# STML451RE.net
KiCad netlist of a schematic drawn in EAGLE
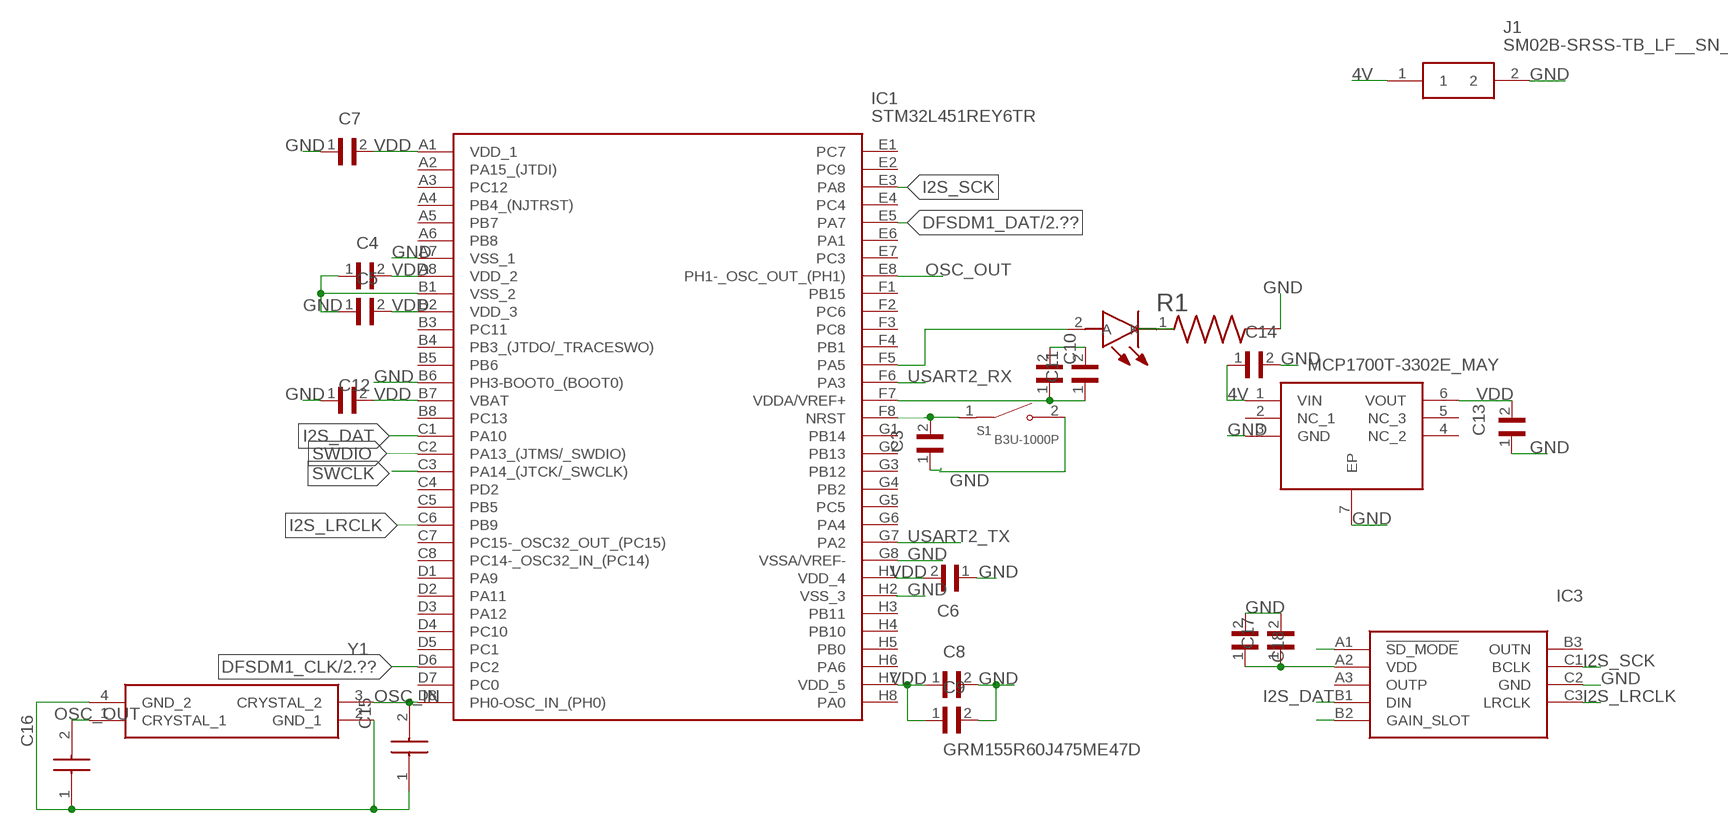
[diagram p0: schematic, sheet 1]
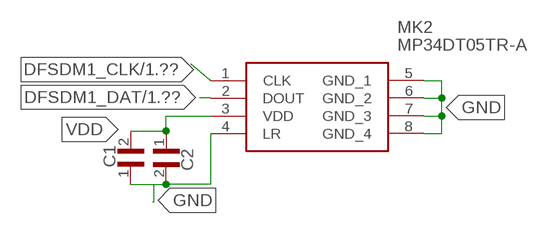
[diagram p1: schematic, sheet 2]

(export (version "E")
  (design (tool "Eeschema 10.0.6"))
  (components
    (comp (ref "C1")
      (value "GRM033C80J104KE15D")
      (footprint "eagle-import:CAPC0603X33N")
      (fields (field (name "DIGI-KEY_PART_NUMBER") "490-10390-1-ND") (field (name "MF") "Murata Electronics"))
      (libsource (lib "eagle-import") (part "GRM033C80J104KE15D"))
    )
    (comp (ref "C2")
      (value "JMK105C6105KV-F")
      (footprint "eagle-import:CAPC1005X55N")
      (fields (field (name "DIGI-KEY_PART_NUMBER") "587-3381-1-ND") (field (name "MF") "Taiyo Yuden"))
      (libsource (lib "eagle-import") (part "JMK105C6105KV-F"))
    )
    (comp (ref "MK2")
      (value "MP34DT05TR-A")
      (footprint "eagle-import:MP34DT05TRA")
      (fields (field (name "MOUSER_PART_NUMBER") "511-MP34DT05TR-A"))
      (libsource (lib "eagle-import") (part "MP34DT05TR-A"))
    )
    (comp (ref "C3")
      (value "GRM033C80J104KE15D")
      (footprint "eagle-import:CAPC0603X33N")
      (fields (field (name "DIGI-KEY_PART_NUMBER") "490-10390-1-ND") (field (name "MF") "Murata Electronics"))
      (libsource (lib "eagle-import") (part "GRM033C80J104KE15D"))
    )
    (comp (ref "C4")
      (value "GRM033C80J104KE15D")
      (footprint "eagle-import:CAPC0603X33N")
      (fields (field (name "DIGI-KEY_PART_NUMBER") "490-10390-1-ND") (field (name "MF") "Murata Electronics"))
      (libsource (lib "eagle-import") (part "GRM033C80J104KE15D"))
    )
    (comp (ref "C5")
      (value "GRM033C80J104KE15D")
      (footprint "eagle-import:CAPC0603X33N")
      (fields (field (name "DIGI-KEY_PART_NUMBER") "490-10390-1-ND") (field (name "MF") "Murata Electronics"))
      (libsource (lib "eagle-import") (part "GRM033C80J104KE15D"))
    )
    (comp (ref "C6")
      (value "GRM033C80J104KE15D")
      (footprint "eagle-import:CAPC0603X33N")
      (fields (field (name "DIGI-KEY_PART_NUMBER") "490-10390-1-ND") (field (name "MF") "Murata Electronics"))
      (libsource (lib "eagle-import") (part "GRM033C80J104KE15D"))
    )
    (comp (ref "C7")
      (value "GRM033C80J104KE15D")
      (footprint "eagle-import:CAPC0603X33N")
      (fields (field (name "DIGI-KEY_PART_NUMBER") "490-10390-1-ND") (field (name "MF") "Murata Electronics"))
      (libsource (lib "eagle-import") (part "GRM033C80J104KE15D"))
    )
    (comp (ref "C8")
      (value "GRM033C80J104KE15D")
      (footprint "eagle-import:CAPC0603X33N")
      (fields (field (name "DIGI-KEY_PART_NUMBER") "490-10390-1-ND") (field (name "MF") "Murata Electronics"))
      (libsource (lib "eagle-import") (part "GRM033C80J104KE15D"))
    )
    (comp (ref "C9")
      (value "GRM155R60J475ME47D")
      (footprint "eagle-import:CAPC1005X60N")
      (fields (field (name "DIGI-KEY_PART_NUMBER") "490-5915-1-ND") (field (name "MF") "Murata"))
      (libsource (lib "eagle-import") (part "GRM155R60J475ME47D"))
    )
    (comp (ref "C10")
      (value "GRM033C80J104KE15D")
      (footprint "eagle-import:CAPC0603X33N")
      (fields (field (name "DIGI-KEY_PART_NUMBER") "490-10390-1-ND") (field (name "MF") "Murata Electronics"))
      (libsource (lib "eagle-import") (part "GRM033C80J104KE15D"))
    )
    (comp (ref "C11")
      (value "JMK105C6105KV-F")
      (footprint "eagle-import:CAPC1005X55N")
      (fields (field (name "DIGI-KEY_PART_NUMBER") "587-3381-1-ND") (field (name "MF") "Taiyo Yuden"))
      (libsource (lib "eagle-import") (part "JMK105C6105KV-F"))
    )
    (comp (ref "C12")
      (value "GRM033C80J104KE15D")
      (footprint "eagle-import:CAPC0603X33N")
      (fields (field (name "DIGI-KEY_PART_NUMBER") "490-10390-1-ND") (field (name "MF") "Murata Electronics"))
      (libsource (lib "eagle-import") (part "GRM033C80J104KE15D"))
    )
    (comp (ref "C13")
      (value "JMK105C6105KV-F")
      (footprint "eagle-import:CAPC1005X55N")
      (fields (field (name "DIGI-KEY_PART_NUMBER") "587-3381-1-ND") (field (name "MF") "Taiyo Yuden"))
      (libsource (lib "eagle-import") (part "JMK105C6105KV-F"))
    )
    (comp (ref "C14")
      (value "JMK105C6105KV-F")
      (footprint "eagle-import:CAPC1005X55N")
      (fields (field (name "DIGI-KEY_PART_NUMBER") "587-3381-1-ND") (field (name "MF") "Taiyo Yuden"))
      (libsource (lib "eagle-import") (part "JMK105C6105KV-F"))
    )
    (comp (ref "C15")
      (value "0101YA120JAT2A")
      (footprint "eagle-import:CAPC0402X22N")
      (fields (field (name "MOUSER_PART_NUMBER") "581-0101YA120JAT2A"))
      (libsource (lib "eagle-import") (part "0101YA120JAT2A"))
    )
    (comp (ref "C16")
      (value "0101YA120JAT2A")
      (footprint "eagle-import:CAPC0402X22N")
      (fields (field (name "MOUSER_PART_NUMBER") "581-0101YA120JAT2A"))
      (libsource (lib "eagle-import") (part "0101YA120JAT2A"))
    )
    (comp (ref "C17")
      (value "GRM033C80J104KE15D")
      (footprint "eagle-import:CAPC0603X33N")
      (fields (field (name "DIGI-KEY_PART_NUMBER") "490-10390-1-ND") (field (name "MF") "Murata Electronics"))
      (libsource (lib "eagle-import") (part "GRM033C80J104KE15D"))
    )
    (comp (ref "C18")
      (value "C0805C106K8PACTU")
      (footprint "eagle-import:CAPC2012X88N")
      (fields (field (name "MF") "KEMET"))
      (libsource (lib "eagle-import") (part "C0805C106K8PACTU"))
    )
    (comp (ref "IC1")
      (value "STM32L451REY6TR")
      (footprint "eagle-import:BGA64C40P8X8_336X366X58")
      (fields (field (name "MOUSER_PART_NUMBER") "511-STM32L451REY6TR"))
      (libsource (lib "eagle-import") (part "STM32L451REY6TR"))
    )
    (comp (ref "IC2")
      (value "MCP1700T-3302E_MAY")
      (footprint "eagle-import:SON65P200X200X90-7N")
      (fields
        (field (name "ARROW_PART_NUMBER") "MCP1700T-3302E/MAY")
        (field (name "MOUSER_PART_NUMBER") "579-MCP1700T3302EMAY")
      )
      (libsource (lib "eagle-import") (part "MCP1700T-3302E_MAY"))
    )
    (comp (ref "IC3")
      (value "MAX98357AEWL+T")
      (footprint "eagle-import:BGA9C40P3X3_144X135X69")
      (fields (field (name "MOUSER_PART_NUMBER") "700-MAX98357AEWL+T"))
      (libsource (lib "eagle-import") (part "MAX98357AEWL+T"))
    )
    (comp (ref "J1")
      (value "SM02B-SRSS-TB_LF__SN_")
      (footprint "eagle-import:SM02B-SRSS-TB")
      (fields (field (name "ARROW_PART_NUMBER") "SM02B-SRSS-TB(LF)(SN)"))
      (libsource (lib "eagle-import") (part "SM02B-SRSS-TB_LF__SN_"))
    )
    (comp (ref "LED1")
      (value "VLMS1500-GS08")
      (footprint "eagle-import:VLMG1500GS08")
      (fields (field (name "MOUSER_PART_NUMBER") "78-VLMS1500-GS08"))
      (libsource (lib "eagle-import") (part "VLMS1500-GS08"))
    )
    (comp (ref "R1")
      (value "CRCW02012K20FKED")
      (footprint "eagle-import:RESC0603X28N")
      (fields (field (name "DIGI-KEY_PART_NUMBER") "541-2.20KAABCT-ND") (field (name "MF") "Vishay"))
      (libsource (lib "eagle-import") (part "CRCW02012K20FKED"))
    )
    (comp (ref "S1")
      (value "B3U-1000P")
      (footprint "eagle-import:SW_B3U-1000P")
      (fields (field (name "DIGI-KEY_PART_NUMBER") "SW1020CT-ND") (field (name "MF") "Omron"))
      (libsource (lib "eagle-import") (part "B3U-1000P"))
    )
    (comp (ref "Y1")
      (value "FL0800008Q")
      (footprint "eagle-import:FL0800008Q")
      (fields (field (name "MOUSER_PART_NUMBER") "729-FL0800008Q"))
      (libsource (lib "eagle-import") (part "FL0800008Q"))
    )
  )
  (nets
    (net (code "1") (name "4V") (class "Default")
      (node (ref "C14") (pin "1") (pinfunction "1_1") (pintype "passive"))
      (node (ref "IC2") (pin "1") (pinfunction "VIN_1") (pintype "bidirectional"))
      (node (ref "J1") (pin "1") (pinfunction "1_1") (pintype "bidirectional"))
    )
    (net (code "2") (name "DFSDM1_CLK") (class "Default")
      (node (ref "IC1") (pin "D6") (pinfunction "PC2_D6") (pintype "bidirectional"))
      (node (ref "MK2") (pin "1") (pinfunction "CLK_1") (pintype "bidirectional"))
    )
    (net (code "3") (name "DFSDM1_DAT") (class "Default")
      (node (ref "IC1") (pin "E5") (pinfunction "PA7_E5") (pintype "bidirectional"))
      (node (ref "MK2") (pin "2") (pinfunction "DOUT_2") (pintype "bidirectional"))
    )
    (net (code "4") (name "GND") (class "Default")
      (node (ref "C12") (pin "1") (pinfunction "1_1") (pintype "passive"))
      (node (ref "C13") (pin "1") (pinfunction "1_1") (pintype "passive"))
      (node (ref "C14") (pin "2") (pinfunction "2_2") (pintype "passive"))
      (node (ref "C15") (pin "1") (pinfunction "1_1") (pintype "bidirectional"))
      (node (ref "C16") (pin "1") (pinfunction "1_1") (pintype "bidirectional"))
      (node (ref "C17") (pin "2") (pinfunction "2_2") (pintype "passive"))
      (node (ref "C18") (pin "2") (pinfunction "2_2") (pintype "passive"))
      (node (ref "C3") (pin "1") (pinfunction "1_1") (pintype "passive"))
      (node (ref "C4") (pin "1") (pinfunction "1_1") (pintype "passive"))
      (node (ref "C5") (pin "1") (pinfunction "1_1") (pintype "passive"))
      (node (ref "C6") (pin "1") (pinfunction "1_1") (pintype "passive"))
      (node (ref "C7") (pin "1") (pinfunction "1_1") (pintype "passive"))
      (node (ref "C8") (pin "2") (pinfunction "2_2") (pintype "passive"))
      (node (ref "C9") (pin "2") (pinfunction "2_2") (pintype "passive"))
      (node (ref "IC1") (pin "A7") (pinfunction "VSS_1_A7") (pintype "bidirectional"))
      (node (ref "IC1") (pin "B1") (pinfunction "VSS_2_B1") (pintype "bidirectional"))
      (node (ref "IC1") (pin "B6") (pinfunction "PH3-BOOT0_(BOOT0)_B6") (pintype "bidirectional"))
      (node (ref "IC1") (pin "G8") (pinfunction "VSSA/VREF-_G8") (pintype "bidirectional"))
      (node (ref "IC1") (pin "H2") (pinfunction "VSS_3_H2") (pintype "bidirectional"))
      (node (ref "IC2") (pin "3") (pinfunction "GND_3") (pintype "bidirectional"))
      (node (ref "IC2") (pin "7") (pinfunction "EP_7") (pintype "bidirectional"))
      (node (ref "IC3") (pin "C2") (pinfunction "GND_C2") (pintype "bidirectional"))
      (node (ref "J1") (pin "2") (pinfunction "2_2") (pintype "bidirectional"))
      (node (ref "MK2") (pin "5") (pinfunction "GND_1_5") (pintype "bidirectional"))
      (node (ref "MK2") (pin "6") (pinfunction "GND_2_6") (pintype "bidirectional"))
      (node (ref "MK2") (pin "7") (pinfunction "GND_3_7") (pintype "bidirectional"))
      (node (ref "MK2") (pin "8") (pinfunction "GND_4_8") (pintype "bidirectional"))
      (node (ref "R1") (pin "2") (pinfunction "2_2") (pintype "passive"))
      (node (ref "Y1") (pin "2") (pinfunction "GND_1_2") (pintype "bidirectional"))
      (node (ref "Y1") (pin "4") (pinfunction "GND_2_4") (pintype "bidirectional"))
    )
    (net (code "5") (name "I2S_DAT") (class "Default")
      (node (ref "IC1") (pin "C1") (pinfunction "PA10_C1") (pintype "bidirectional"))
      (node (ref "IC3") (pin "B1") (pinfunction "DIN_B1") (pintype "bidirectional"))
    )
    (net (code "6") (name "I2S_LRCLK") (class "Default")
      (node (ref "IC1") (pin "C6") (pinfunction "PB9_C6") (pintype "bidirectional"))
      (node (ref "IC3") (pin "C3") (pinfunction "LRCLK_C3") (pintype "bidirectional"))
    )
    (net (code "7") (name "I2S_SCK") (class "Default")
      (node (ref "IC1") (pin "E3") (pinfunction "PA8_E3") (pintype "bidirectional"))
      (node (ref "IC3") (pin "C1") (pinfunction "BCLK_C1") (pintype "bidirectional"))
    )
    (net (code "8") (name "Net-(C3-Pad2)") (class "Default")
      (node (ref "C3") (pin "2") (pinfunction "2_2") (pintype "passive"))
      (node (ref "S1") (pin "1") (pinfunction "1_1") (pintype "passive"))
    )
    (net (code "9") (name "Net-(C10-Pad2)") (class "Default")
      (node (ref "C10") (pin "2") (pinfunction "2_2") (pintype "passive"))
      (node (ref "C11") (pin "2") (pinfunction "2_2") (pintype "passive"))
    )
    (net (code "10") (name "Net-(IC1-PA5)") (class "Default")
      (node (ref "IC1") (pin "F5") (pinfunction "PA5_F5") (pintype "bidirectional"))
      (node (ref "LED1") (pin "2") (pinfunction "A_2") (pintype "bidirectional"))
    )
    (net (code "11") (name "Net-(IC1-VDDA{slash}VREF+)") (class "Default")
      (node (ref "C10") (pin "1") (pinfunction "1_1") (pintype "passive"))
      (node (ref "C11") (pin "1") (pinfunction "1_1") (pintype "passive"))
      (node (ref "IC1") (pin "F7") (pinfunction "VDDA/VREF+_F7") (pintype "bidirectional"))
    )
    (net (code "12") (name "Net-(IC3-VDD)") (class "Default")
      (node (ref "C17") (pin "1") (pinfunction "1_1") (pintype "passive"))
      (node (ref "C18") (pin "1") (pinfunction "1_1") (pintype "passive"))
      (node (ref "IC3") (pin "A2") (pinfunction "VDD_A2") (pintype "bidirectional"))
    )
    (net (code "13") (name "Net-(LED1-K)") (class "Default")
      (node (ref "LED1") (pin "1") (pinfunction "K_1") (pintype "bidirectional"))
      (node (ref "R1") (pin "1") (pinfunction "1_1") (pintype "passive"))
    )
    (net (code "14") (name "Net-(MK2-LR)") (class "Default")
      (node (ref "C1") (pin "1") (pinfunction "1_1") (pintype "passive"))
      (node (ref "C2") (pin "2") (pinfunction "2_2") (pintype "passive"))
      (node (ref "MK2") (pin "4") (pinfunction "LR_4") (pintype "bidirectional"))
    )
    (net (code "15") (name "OSC_IN") (class "Default")
      (node (ref "C15") (pin "2") (pinfunction "2_2") (pintype "bidirectional"))
      (node (ref "IC1") (pin "D8") (pinfunction "PH0-OSC_IN_(PH0)_D8") (pintype "bidirectional"))
      (node (ref "Y1") (pin "3") (pinfunction "CRYSTAL_2_3") (pintype "bidirectional"))
    )
    (net (code "16") (name "OSC_OUT") (class "Default")
      (node (ref "C16") (pin "2") (pinfunction "2_2") (pintype "bidirectional"))
      (node (ref "IC1") (pin "E8") (pinfunction "PH1-_OSC_OUT_(PH1)_E8") (pintype "bidirectional"))
      (node (ref "Y1") (pin "1") (pinfunction "CRYSTAL_1_1") (pintype "bidirectional"))
    )
    (net (code "17") (name "SWCLK") (class "Default")
      (node (ref "IC1") (pin "C3") (pinfunction "PA14_(JTCK/_SWCLK)_C3") (pintype "bidirectional"))
    )
    (net (code "18") (name "SWDIO") (class "Default")
      (node (ref "IC1") (pin "C2") (pinfunction "PA13_(JTMS/_SWDIO)_C2") (pintype "bidirectional"))
    )
    (net (code "19") (name "USART2_RX") (class "Default")
      (node (ref "IC1") (pin "F6") (pinfunction "PA3_F6") (pintype "bidirectional"))
    )
    (net (code "20") (name "USART2_TX") (class "Default")
      (node (ref "IC1") (pin "G7") (pinfunction "PA2_G7") (pintype "bidirectional"))
    )
    (net (code "21") (name "VDD") (class "Default")
      (node (ref "C1") (pin "2") (pinfunction "2_2") (pintype "passive"))
      (node (ref "C12") (pin "2") (pinfunction "2_2") (pintype "passive"))
      (node (ref "C13") (pin "2") (pinfunction "2_2") (pintype "passive"))
      (node (ref "C2") (pin "1") (pinfunction "1_1") (pintype "passive"))
      (node (ref "C4") (pin "2") (pinfunction "2_2") (pintype "passive"))
      (node (ref "C5") (pin "2") (pinfunction "2_2") (pintype "passive"))
      (node (ref "C6") (pin "2") (pinfunction "2_2") (pintype "passive"))
      (node (ref "C7") (pin "2") (pinfunction "2_2") (pintype "passive"))
      (node (ref "C8") (pin "1") (pinfunction "1_1") (pintype "passive"))
      (node (ref "C9") (pin "1") (pinfunction "1_1") (pintype "passive"))
      (node (ref "IC1") (pin "A1") (pinfunction "VDD_1_A1") (pintype "bidirectional"))
      (node (ref "IC1") (pin "A8") (pinfunction "VDD_2_A8") (pintype "bidirectional"))
      (node (ref "IC1") (pin "B2") (pinfunction "VDD_3_B2") (pintype "bidirectional"))
      (node (ref "IC1") (pin "B7") (pinfunction "VBAT_B7") (pintype "bidirectional"))
      (node (ref "IC1") (pin "H1") (pinfunction "VDD_4_H1") (pintype "bidirectional"))
      (node (ref "IC1") (pin "H7") (pinfunction "VDD_5_H7") (pintype "bidirectional"))
      (node (ref "IC2") (pin "6") (pinfunction "VOUT_6") (pintype "bidirectional"))
      (node (ref "MK2") (pin "3") (pinfunction "VDD_3") (pintype "bidirectional"))
    )
    (net (code "22") (name "unconnected-(IC1-NRST-PadF8)") (class "Default")
      (node (ref "IC1") (pin "F8") (pinfunction "NRST_F8") (pintype "bidirectional"))
    )
    (net (code "23") (name "unconnected-(IC1-PA0-PadH8)") (class "Default")
      (node (ref "IC1") (pin "H8") (pinfunction "PA0_H8") (pintype "bidirectional"))
    )
    (net (code "24") (name "unconnected-(IC1-PA1-PadE6)") (class "Default")
      (node (ref "IC1") (pin "E6") (pinfunction "PA1_E6") (pintype "bidirectional"))
    )
    (net (code "25") (name "unconnected-(IC1-PA4-PadG6)") (class "Default")
      (node (ref "IC1") (pin "G6") (pinfunction "PA4_G6") (pintype "bidirectional"))
    )
    (net (code "26") (name "unconnected-(IC1-PA6-PadH6)") (class "Default")
      (node (ref "IC1") (pin "H6") (pinfunction "PA6_H6") (pintype "bidirectional"))
    )
    (net (code "27") (name "unconnected-(IC1-PA9-PadD1)") (class "Default")
      (node (ref "IC1") (pin "D1") (pinfunction "PA9_D1") (pintype "bidirectional"))
    )
    (net (code "28") (name "unconnected-(IC1-PA11-PadD2)") (class "Default")
      (node (ref "IC1") (pin "D2") (pinfunction "PA11_D2") (pintype "bidirectional"))
    )
    (net (code "29") (name "unconnected-(IC1-PA12-PadD3)") (class "Default")
      (node (ref "IC1") (pin "D3") (pinfunction "PA12_D3") (pintype "bidirectional"))
    )
    (net (code "30") (name "unconnected-(IC1-PA15_(JTDI)-PadA2)") (class "Default")
      (node (ref "IC1") (pin "A2") (pinfunction "PA15_(JTDI)_A2") (pintype "bidirectional"))
    )
    (net (code "31") (name "unconnected-(IC1-PB0-PadH5)") (class "Default")
      (node (ref "IC1") (pin "H5") (pinfunction "PB0_H5") (pintype "bidirectional"))
    )
    (net (code "32") (name "unconnected-(IC1-PB1-PadF4)") (class "Default")
      (node (ref "IC1") (pin "F4") (pinfunction "PB1_F4") (pintype "bidirectional"))
    )
    (net (code "33") (name "unconnected-(IC1-PB2-PadG4)") (class "Default")
      (node (ref "IC1") (pin "G4") (pinfunction "PB2_G4") (pintype "bidirectional"))
    )
    (net (code "34") (name "unconnected-(IC1-PB3_(JTDO{slash}_TRACESWO)-PadB4)") (class "Default")
      (node (ref "IC1") (pin "B4") (pinfunction "PB3_(JTDO/_TRACESWO)_B4") (pintype "bidirectional"))
    )
    (net (code "35") (name "unconnected-(IC1-PB4_(NJTRST)-PadA4)") (class "Default")
      (node (ref "IC1") (pin "A4") (pinfunction "PB4_(NJTRST)_A4") (pintype "bidirectional"))
    )
    (net (code "36") (name "unconnected-(IC1-PB5-PadC5)") (class "Default")
      (node (ref "IC1") (pin "C5") (pinfunction "PB5_C5") (pintype "bidirectional"))
    )
    (net (code "37") (name "unconnected-(IC1-PB6-PadB5)") (class "Default")
      (node (ref "IC1") (pin "B5") (pinfunction "PB6_B5") (pintype "bidirectional"))
    )
    (net (code "38") (name "unconnected-(IC1-PB7-PadA5)") (class "Default")
      (node (ref "IC1") (pin "A5") (pinfunction "PB7_A5") (pintype "bidirectional"))
    )
    (net (code "39") (name "unconnected-(IC1-PB8-PadA6)") (class "Default")
      (node (ref "IC1") (pin "A6") (pinfunction "PB8_A6") (pintype "bidirectional"))
    )
    (net (code "40") (name "unconnected-(IC1-PB10-PadH4)") (class "Default")
      (node (ref "IC1") (pin "H4") (pinfunction "PB10_H4") (pintype "bidirectional"))
    )
    (net (code "41") (name "unconnected-(IC1-PB11-PadH3)") (class "Default")
      (node (ref "IC1") (pin "H3") (pinfunction "PB11_H3") (pintype "bidirectional"))
    )
    (net (code "42") (name "unconnected-(IC1-PB12-PadG3)") (class "Default")
      (node (ref "IC1") (pin "G3") (pinfunction "PB12_G3") (pintype "bidirectional"))
    )
    (net (code "43") (name "unconnected-(IC1-PB13-PadG2)") (class "Default")
      (node (ref "IC1") (pin "G2") (pinfunction "PB13_G2") (pintype "bidirectional"))
    )
    (net (code "44") (name "unconnected-(IC1-PB14-PadG1)") (class "Default")
      (node (ref "IC1") (pin "G1") (pinfunction "PB14_G1") (pintype "bidirectional"))
    )
    (net (code "45") (name "unconnected-(IC1-PB15-PadF1)") (class "Default")
      (node (ref "IC1") (pin "F1") (pinfunction "PB15_F1") (pintype "bidirectional"))
    )
    (net (code "46") (name "unconnected-(IC1-PC0-PadD7)") (class "Default")
      (node (ref "IC1") (pin "D7") (pinfunction "PC0_D7") (pintype "bidirectional"))
    )
    (net (code "47") (name "unconnected-(IC1-PC1-PadD5)") (class "Default")
      (node (ref "IC1") (pin "D5") (pinfunction "PC1_D5") (pintype "bidirectional"))
    )
    (net (code "48") (name "unconnected-(IC1-PC3-PadE7)") (class "Default")
      (node (ref "IC1") (pin "E7") (pinfunction "PC3_E7") (pintype "bidirectional"))
    )
    (net (code "49") (name "unconnected-(IC1-PC4-PadE4)") (class "Default")
      (node (ref "IC1") (pin "E4") (pinfunction "PC4_E4") (pintype "bidirectional"))
    )
    (net (code "50") (name "unconnected-(IC1-PC5-PadG5)") (class "Default")
      (node (ref "IC1") (pin "G5") (pinfunction "PC5_G5") (pintype "bidirectional"))
    )
    (net (code "51") (name "unconnected-(IC1-PC6-PadF2)") (class "Default")
      (node (ref "IC1") (pin "F2") (pinfunction "PC6_F2") (pintype "bidirectional"))
    )
    (net (code "52") (name "unconnected-(IC1-PC7-PadE1)") (class "Default")
      (node (ref "IC1") (pin "E1") (pinfunction "PC7_E1") (pintype "bidirectional"))
    )
    (net (code "53") (name "unconnected-(IC1-PC8-PadF3)") (class "Default")
      (node (ref "IC1") (pin "F3") (pinfunction "PC8_F3") (pintype "bidirectional"))
    )
    (net (code "54") (name "unconnected-(IC1-PC9-PadE2)") (class "Default")
      (node (ref "IC1") (pin "E2") (pinfunction "PC9_E2") (pintype "bidirectional"))
    )
    (net (code "55") (name "unconnected-(IC1-PC10-PadD4)") (class "Default")
      (node (ref "IC1") (pin "D4") (pinfunction "PC10_D4") (pintype "bidirectional"))
    )
    (net (code "56") (name "unconnected-(IC1-PC11-PadB3)") (class "Default")
      (node (ref "IC1") (pin "B3") (pinfunction "PC11_B3") (pintype "bidirectional"))
    )
    (net (code "57") (name "unconnected-(IC1-PC12-PadA3)") (class "Default")
      (node (ref "IC1") (pin "A3") (pinfunction "PC12_A3") (pintype "bidirectional"))
    )
    (net (code "58") (name "unconnected-(IC1-PC13-PadB8)") (class "Default")
      (node (ref "IC1") (pin "B8") (pinfunction "PC13_B8") (pintype "bidirectional"))
    )
    (net (code "59") (name "unconnected-(IC1-PC14-_OSC32_IN_(PC14)-PadC8)") (class "Default")
      (node (ref "IC1") (pin "C8") (pinfunction "PC14-_OSC32_IN_(PC14)_C8") (pintype "bidirectional"))
    )
    (net (code "60") (name "unconnected-(IC1-PC15-_OSC32_OUT_(PC15)-PadC7)") (class "Default")
      (node (ref "IC1") (pin "C7") (pinfunction "PC15-_OSC32_OUT_(PC15)_C7") (pintype "bidirectional"))
    )
    (net (code "61") (name "unconnected-(IC1-PD2-PadC4)") (class "Default")
      (node (ref "IC1") (pin "C4") (pinfunction "PD2_C4") (pintype "bidirectional"))
    )
    (net (code "62") (name "unconnected-(IC2-NC_1-Pad2)") (class "Default")
      (node (ref "IC2") (pin "2") (pinfunction "NC_1_2") (pintype "bidirectional"))
    )
    (net (code "63") (name "unconnected-(IC2-NC_2-Pad4)") (class "Default")
      (node (ref "IC2") (pin "4") (pinfunction "NC_2_4") (pintype "bidirectional"))
    )
    (net (code "64") (name "unconnected-(IC2-NC_3-Pad5)") (class "Default")
      (node (ref "IC2") (pin "5") (pinfunction "NC_3_5") (pintype "bidirectional"))
    )
    (net (code "65") (name "unconnected-(IC3-GAIN_SLOT-PadB2)") (class "Default")
      (node (ref "IC3") (pin "B2") (pinfunction "GAIN_SLOT_B2") (pintype "bidirectional"))
    )
    (net (code "66") (name "unconnected-(IC3-OUTN-PadB3)") (class "Default")
      (node (ref "IC3") (pin "B3") (pinfunction "OUTN_B3") (pintype "bidirectional"))
    )
    (net (code "67") (name "unconnected-(IC3-OUTP-PadA3)") (class "Default")
      (node (ref "IC3") (pin "A3") (pinfunction "OUTP_A3") (pintype "bidirectional"))
    )
    (net (code "68") (name "unconnected-(IC3-~{SD_MODE}-PadA1)") (class "Default")
      (node (ref "IC3") (pin "A1") (pinfunction "~{SD_MODE}_A1") (pintype "bidirectional"))
    )
    (net (code "69") (name "unconnected-(S1-Pad2)") (class "Default")
      (node (ref "S1") (pin "2") (pinfunction "2_2") (pintype "passive"))
    )
  )
)
